# Brakeout_board_-_wire_connection.net
KiCad netlist of a schematic drawn in EAGLE
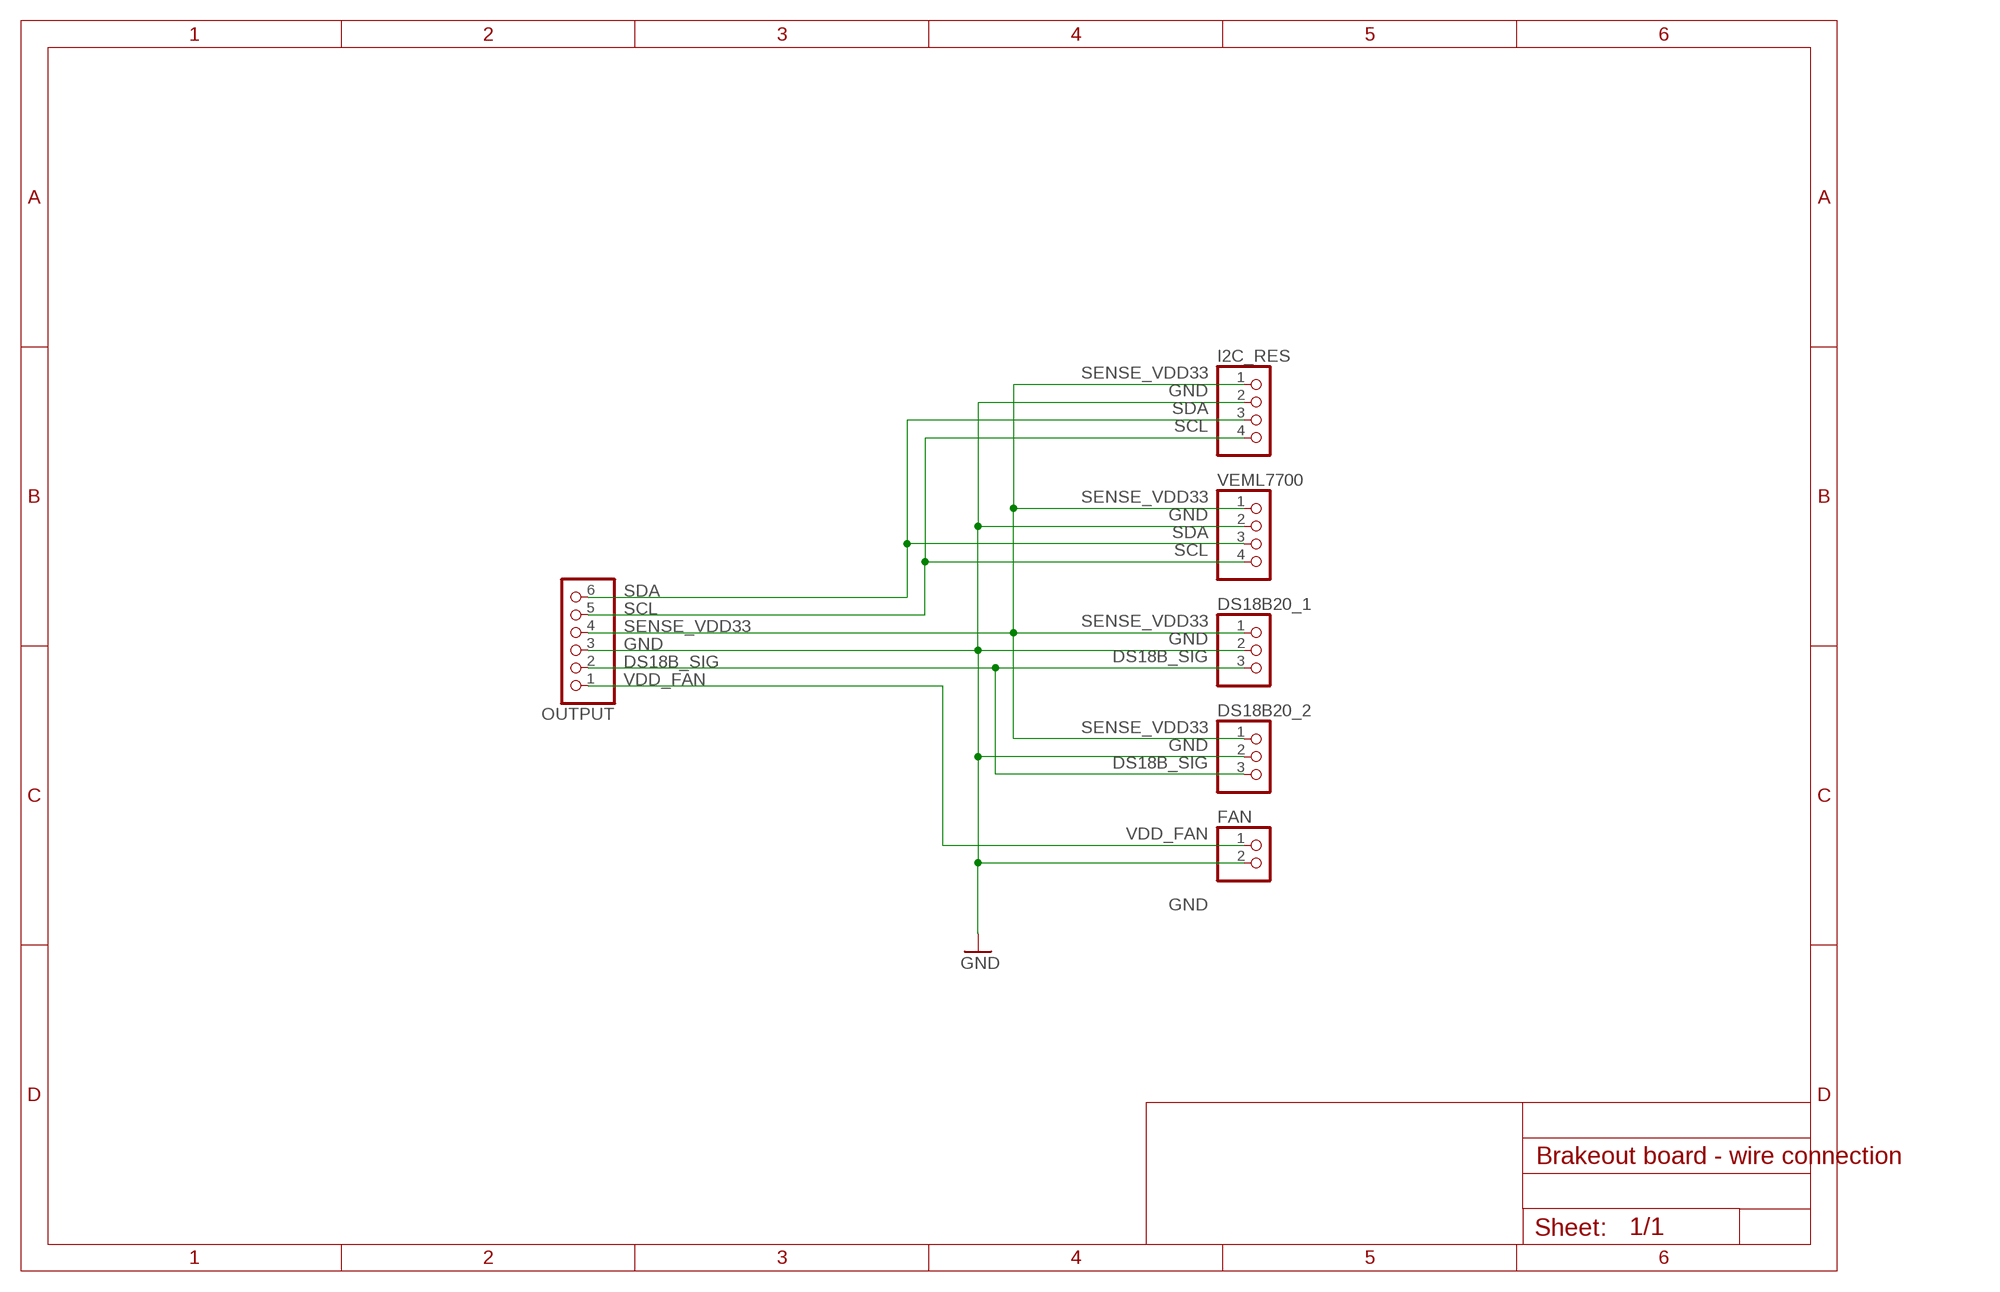
[diagram p0: schematic, sheet 1]

(export (version "E")
  (design (tool "Eeschema 10.0.6"))
  (components
    (comp (ref "DS18B20_1")
      (value "PINHD-1X3")
      (footprint "eagle-import:1X03")
      (libsource (lib "eagle-import") (part "PINHD-1X3"))
    )
    (comp (ref "DS18B20_2")
      (value "PINHD-1X3")
      (footprint "eagle-import:1X03")
      (libsource (lib "eagle-import") (part "PINHD-1X3"))
    )
    (comp (ref "FAN")
      (value "PINHD-1X2")
      (footprint "eagle-import:1X02")
      (libsource (lib "eagle-import") (part "PINHD-1X2"))
    )
    (comp (ref "I2C_RES")
      (value "PINHD-1X4")
      (footprint "eagle-import:1X04")
      (libsource (lib "eagle-import") (part "PINHD-1X4"))
    )
    (comp (ref "OUTPUT")
      (value "PINHD-1X6")
      (footprint "eagle-import:1X06")
      (libsource (lib "eagle-import") (part "PINHD-1X6"))
    )
    (comp (ref "VEML7700")
      (value "PINHD-1X4")
      (footprint "eagle-import:1X04")
      (libsource (lib "eagle-import") (part "PINHD-1X4"))
    )
  )
  (nets
    (net (code "1") (name "/DS18B_SIG") (class "Default")
      (node (ref "DS18B20_1") (pin "3") (pinfunction "3_3") (pintype "passive"))
      (node (ref "DS18B20_2") (pin "3") (pinfunction "3_3") (pintype "passive"))
      (node (ref "OUTPUT") (pin "2") (pinfunction "2_2") (pintype "passive"))
    )
    (net (code "2") (name "/SCL") (class "Default")
      (node (ref "I2C_RES") (pin "4") (pinfunction "4_4") (pintype "passive"))
      (node (ref "OUTPUT") (pin "5") (pinfunction "5_5") (pintype "passive"))
      (node (ref "VEML7700") (pin "4") (pinfunction "4_4") (pintype "passive"))
    )
    (net (code "3") (name "/SDA") (class "Default")
      (node (ref "I2C_RES") (pin "3") (pinfunction "3_3") (pintype "passive"))
      (node (ref "OUTPUT") (pin "6") (pinfunction "6_6") (pintype "passive"))
      (node (ref "VEML7700") (pin "3") (pinfunction "3_3") (pintype "passive"))
    )
    (net (code "4") (name "/SENSE_VDD33") (class "Default")
      (node (ref "DS18B20_1") (pin "1") (pinfunction "1_1") (pintype "passive"))
      (node (ref "DS18B20_2") (pin "1") (pinfunction "1_1") (pintype "passive"))
      (node (ref "I2C_RES") (pin "1") (pinfunction "1_1") (pintype "passive"))
      (node (ref "OUTPUT") (pin "4") (pinfunction "4_4") (pintype "passive"))
      (node (ref "VEML7700") (pin "1") (pinfunction "1_1") (pintype "passive"))
    )
    (net (code "5") (name "/VDD_FAN") (class "Default")
      (node (ref "FAN") (pin "1") (pinfunction "1_1") (pintype "passive"))
      (node (ref "OUTPUT") (pin "1") (pinfunction "1_1") (pintype "passive"))
    )
    (net (code "6") (name "GND") (class "Default")
      (node (ref "DS18B20_1") (pin "2") (pinfunction "2_2") (pintype "passive"))
      (node (ref "DS18B20_2") (pin "2") (pinfunction "2_2") (pintype "passive"))
      (node (ref "FAN") (pin "2") (pinfunction "2_2") (pintype "passive"))
      (node (ref "I2C_RES") (pin "2") (pinfunction "2_2") (pintype "passive"))
      (node (ref "OUTPUT") (pin "3") (pinfunction "3_3") (pintype "passive"))
      (node (ref "VEML7700") (pin "2") (pinfunction "2_2") (pintype "passive"))
    )
  )
)
